# DoorALIM.net
KiCad netlist of a schematic drawn in EAGLE
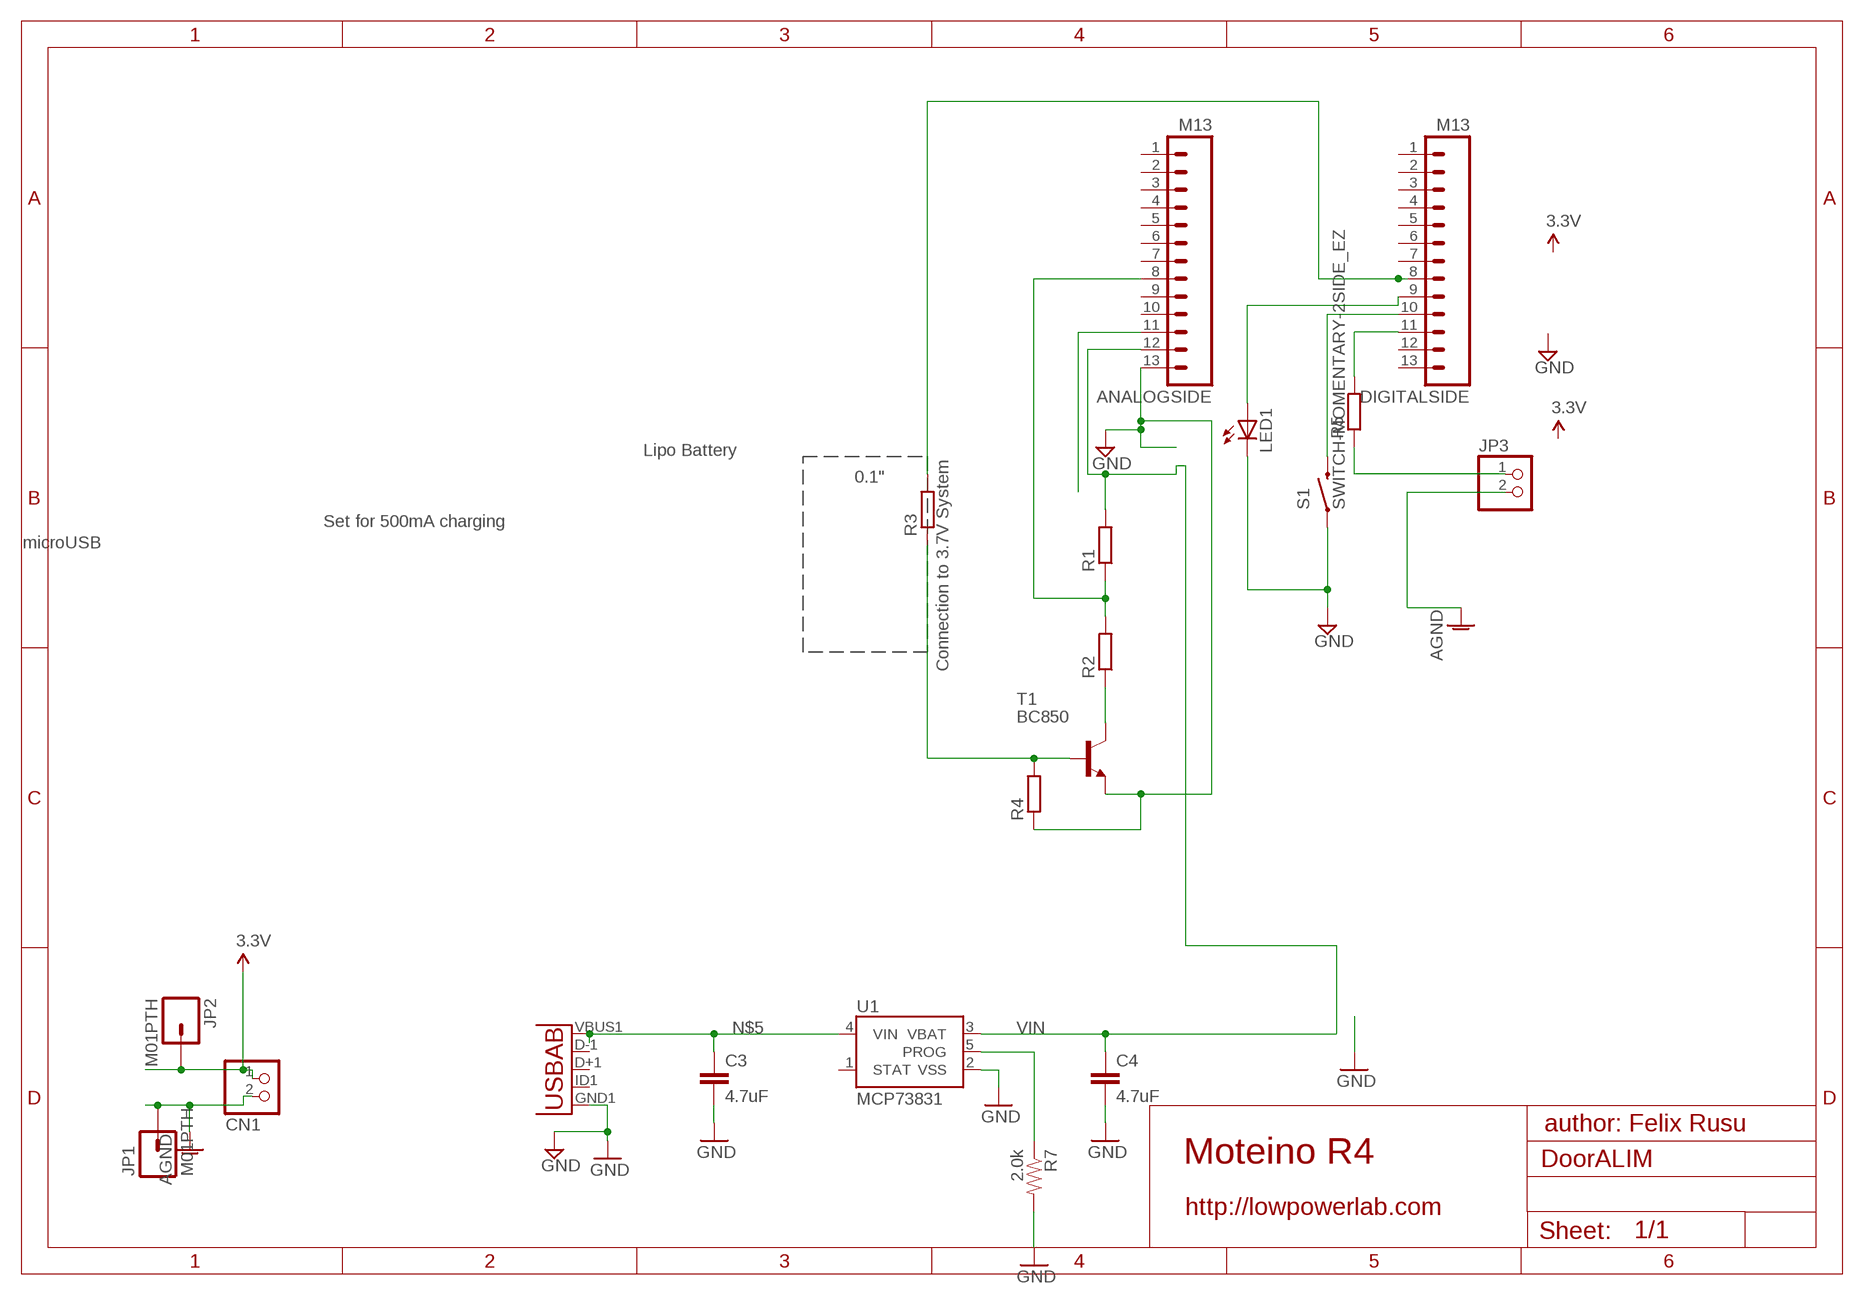
[diagram p0: schematic, sheet 1]

(export (version "E")
  (design (tool "Eeschema 10.0.6"))
  (components
    (comp (ref "ANALOGSIDE")
      (value "M13")
      (footprint "eagle-import:1X13")
      (libsource (lib "eagle-import") (part "M13"))
    )
    (comp (ref "C3")
      (value "4.7uF")
      (footprint "eagle-import:0603-CAP")
      (libsource (lib "eagle-import") (part "4.7UF-6.3V-10%(0603)0603"))
    )
    (comp (ref "C4")
      (value "4.7uF")
      (footprint "eagle-import:0603-CAP")
      (libsource (lib "eagle-import") (part "4.7UF-6.3V-10%(0603)0603"))
    )
    (comp (ref "CN1")
      (value "JST_2PIN-SMT")
      (footprint "eagle-import:JST-PH-2-SMT")
      (libsource (lib "eagle-import") (part "JST_2PIN-SMT"))
    )
    (comp (ref "DIGITALSIDE")
      (value "M13")
      (footprint "eagle-import:1X13")
      (libsource (lib "eagle-import") (part "M13"))
    )
    (comp (ref "JP1")
      (value "M01PTH")
      (footprint "eagle-import:1X01")
      (libsource (lib "eagle-import") (part "M01PTH"))
    )
    (comp (ref "JP2")
      (value "M01PTH")
      (footprint "eagle-import:1X01")
      (libsource (lib "eagle-import") (part "M01PTH"))
    )
    (comp (ref "JP3")
      (value "PINHD-1X2")
      (footprint "eagle-import:1X02")
      (libsource (lib "eagle-import") (part "PINHD-1X2"))
    )
    (comp (ref "JP9")
      (value "Micro USB")
      (footprint "eagle-import:USB-AB-MICRO-SMD_V03")
      (libsource (lib "eagle-import") (part "USB-ABCONN-11794"))
    )
    (comp (ref "LED1")
      (value "LED3MM")
      (footprint "eagle-import:LED3MM")
      (libsource (lib "eagle-import") (part "LED3MM"))
    )
    (comp (ref "R1")
      (value "R-EU_0204/7")
      (footprint "eagle-import:0204_7")
      (libsource (lib "eagle-import") (part "R-EU_0204/7"))
    )
    (comp (ref "R2")
      (value "R-EU_0204/7")
      (footprint "eagle-import:0204_7")
      (libsource (lib "eagle-import") (part "R-EU_0204/7"))
    )
    (comp (ref "R3")
      (value "R-EU_M1206")
      (footprint "eagle-import:M1206")
      (libsource (lib "eagle-import") (part "R-EU_M1206"))
    )
    (comp (ref "R4")
      (value "R-EU_M1206")
      (footprint "eagle-import:M1206")
      (libsource (lib "eagle-import") (part "R-EU_M1206"))
    )
    (comp (ref "R5")
      (value "R-EU_0204/7")
      (footprint "eagle-import:0204_7")
      (libsource (lib "eagle-import") (part "R-EU_0204/7"))
    )
    (comp (ref "R7")
      (value "2.0k")
      (footprint "eagle-import:0603-RES")
      (libsource (lib "eagle-import") (part "2.0KOHM1/10W5%(0603)"))
    )
    (comp (ref "S1")
      (value "SWITCH-MOMENTARY-2SIDE_EZ")
      (footprint "eagle-import:TACTILE-PTH-SIDEEZ")
      (libsource (lib "eagle-import") (part "SWITCH-MOMENTARY-2SIDE_EZ"))
    )
    (comp (ref "T1")
      (value "BC850")
      (footprint "eagle-import:SOT23")
      (libsource (lib "eagle-import") (part "BC850"))
    )
    (comp (ref "U1")
      (value "MCP73831")
      (footprint "eagle-import:SOT23-5")
      (libsource (lib "eagle-import") (part "MCP73831"))
    )
  )
  (nets
    (net (code "1") (name "/N$5") (class "Default")
      (node (ref "C3") (pin "1") (pinfunction "1_1") (pintype "passive"))
      (node (ref "JP9") (pin "VBUS1") (pinfunction "VBUS_VBUS1") (pintype "bidirectional"))
      (node (ref "U1") (pin "4") (pinfunction "VIN_4") (pintype "power_in"))
    )
    (net (code "2") (name "/VIN") (class "Default")
      (node (ref "ANALOGSIDE") (pin "12") (pinfunction "12_12") (pintype "passive"))
      (node (ref "C4") (pin "1") (pinfunction "1_1") (pintype "passive"))
      (node (ref "R1") (pin "2") (pinfunction "2_2") (pintype "passive"))
      (node (ref "U1") (pin "3") (pinfunction "VBAT_3") (pintype "power_in"))
    )
    (net (code "3") (name "3.3V") (class "Default")
      (node (ref "CN1") (pin "1") (pinfunction "2_1") (pintype "passive"))
      (node (ref "JP2") (pin "1") (pinfunction "1_1") (pintype "passive"))
    )
    (net (code "4") (name "AGND") (class "Default")
      (node (ref "CN1") (pin "2") (pinfunction "1_2") (pintype "passive"))
      (node (ref "JP1") (pin "1") (pinfunction "1_1") (pintype "passive"))
      (node (ref "JP3") (pin "2") (pinfunction "2_2") (pintype "passive"))
    )
    (net (code "5") (name "GND") (class "Default")
      (node (ref "ANALOGSIDE") (pin "13") (pinfunction "13_13") (pintype "passive"))
      (node (ref "C3") (pin "2") (pinfunction "2_2") (pintype "passive"))
      (node (ref "C4") (pin "2") (pinfunction "2_2") (pintype "passive"))
      (node (ref "JP9") (pin "GND1") (pinfunction "GND_GND1") (pintype "bidirectional"))
      (node (ref "LED1") (pin "K") (pinfunction "C_K") (pintype "passive"))
      (node (ref "R4") (pin "1") (pinfunction "1_1") (pintype "passive"))
      (node (ref "R7") (pin "2") (pinfunction "2_2") (pintype "passive"))
      (node (ref "S1") (pin "1") (pinfunction "1_1") (pintype "passive"))
      (node (ref "T1") (pin "2") (pinfunction "E_2") (pintype "passive"))
      (node (ref "U1") (pin "2") (pinfunction "VSS_2") (pintype "power_in"))
    )
    (net (code "6") (name "Net-(ANALOGSIDE-Pad8)") (class "Default")
      (node (ref "ANALOGSIDE") (pin "8") (pinfunction "8_8") (pintype "passive"))
      (node (ref "R1") (pin "1") (pinfunction "1_1") (pintype "passive"))
      (node (ref "R2") (pin "2") (pinfunction "2_2") (pintype "passive"))
    )
    (net (code "7") (name "Net-(DIGITALSIDE-Pad8)") (class "Default")
      (node (ref "DIGITALSIDE") (pin "8") (pinfunction "8_8") (pintype "passive"))
      (node (ref "R3") (pin "2") (pinfunction "2_2") (pintype "passive"))
    )
    (net (code "8") (name "Net-(DIGITALSIDE-Pad9)") (class "Default")
      (node (ref "DIGITALSIDE") (pin "9") (pinfunction "9_9") (pintype "passive"))
      (node (ref "LED1") (pin "A") (pinfunction "A_A") (pintype "passive"))
    )
    (net (code "9") (name "Net-(DIGITALSIDE-Pad10)") (class "Default")
      (node (ref "DIGITALSIDE") (pin "10") (pinfunction "10_10") (pintype "passive"))
      (node (ref "S1") (pin "2") (pinfunction "2_2") (pintype "passive"))
    )
    (net (code "10") (name "Net-(DIGITALSIDE-Pad11)") (class "Default")
      (node (ref "DIGITALSIDE") (pin "11") (pinfunction "11_11") (pintype "passive"))
      (node (ref "R5") (pin "2") (pinfunction "2_2") (pintype "passive"))
    )
    (net (code "11") (name "Net-(JP3-Pad1)") (class "Default")
      (node (ref "JP3") (pin "1") (pinfunction "1_1") (pintype "passive"))
      (node (ref "R5") (pin "1") (pinfunction "1_1") (pintype "passive"))
    )
    (net (code "12") (name "Net-(T1-B)") (class "Default")
      (node (ref "R3") (pin "1") (pinfunction "1_1") (pintype "passive"))
      (node (ref "R4") (pin "2") (pinfunction "2_2") (pintype "passive"))
      (node (ref "T1") (pin "1") (pinfunction "B_1") (pintype "passive"))
    )
    (net (code "13") (name "Net-(T1-C)") (class "Default")
      (node (ref "R2") (pin "1") (pinfunction "1_1") (pintype "passive"))
      (node (ref "T1") (pin "3") (pinfunction "C_3") (pintype "passive"))
    )
    (net (code "14") (name "Net-(U1-PROG)") (class "Default")
      (node (ref "R7") (pin "1") (pinfunction "1_1") (pintype "passive"))
      (node (ref "U1") (pin "5") (pinfunction "PROG_5") (pintype "input"))
    )
    (net (code "15") (name "unconnected-(ANALOGSIDE-Pad1)") (class "Default")
      (node (ref "ANALOGSIDE") (pin "1") (pinfunction "1_1") (pintype "passive"))
    )
    (net (code "16") (name "unconnected-(ANALOGSIDE-Pad2)") (class "Default")
      (node (ref "ANALOGSIDE") (pin "2") (pinfunction "2_2") (pintype "passive"))
    )
    (net (code "17") (name "unconnected-(ANALOGSIDE-Pad3)") (class "Default")
      (node (ref "ANALOGSIDE") (pin "3") (pinfunction "3_3") (pintype "passive"))
    )
    (net (code "18") (name "unconnected-(ANALOGSIDE-Pad4)") (class "Default")
      (node (ref "ANALOGSIDE") (pin "4") (pinfunction "4_4") (pintype "passive"))
    )
    (net (code "19") (name "unconnected-(ANALOGSIDE-Pad5)") (class "Default")
      (node (ref "ANALOGSIDE") (pin "5") (pinfunction "5_5") (pintype "passive"))
    )
    (net (code "20") (name "unconnected-(ANALOGSIDE-Pad6)") (class "Default")
      (node (ref "ANALOGSIDE") (pin "6") (pinfunction "6_6") (pintype "passive"))
    )
    (net (code "21") (name "unconnected-(ANALOGSIDE-Pad7)") (class "Default")
      (node (ref "ANALOGSIDE") (pin "7") (pinfunction "7_7") (pintype "passive"))
    )
    (net (code "22") (name "unconnected-(ANALOGSIDE-Pad9)") (class "Default")
      (node (ref "ANALOGSIDE") (pin "9") (pinfunction "9_9") (pintype "passive"))
    )
    (net (code "23") (name "unconnected-(ANALOGSIDE-Pad10)") (class "Default")
      (node (ref "ANALOGSIDE") (pin "10") (pinfunction "10_10") (pintype "passive"))
    )
    (net (code "24") (name "unconnected-(ANALOGSIDE-Pad11)") (class "Default")
      (node (ref "ANALOGSIDE") (pin "11") (pinfunction "11_11") (pintype "passive"))
    )
    (net (code "25") (name "unconnected-(DIGITALSIDE-Pad1)") (class "Default")
      (node (ref "DIGITALSIDE") (pin "1") (pinfunction "1_1") (pintype "passive"))
    )
    (net (code "26") (name "unconnected-(DIGITALSIDE-Pad2)") (class "Default")
      (node (ref "DIGITALSIDE") (pin "2") (pinfunction "2_2") (pintype "passive"))
    )
    (net (code "27") (name "unconnected-(DIGITALSIDE-Pad3)") (class "Default")
      (node (ref "DIGITALSIDE") (pin "3") (pinfunction "3_3") (pintype "passive"))
    )
    (net (code "28") (name "unconnected-(DIGITALSIDE-Pad4)") (class "Default")
      (node (ref "DIGITALSIDE") (pin "4") (pinfunction "4_4") (pintype "passive"))
    )
    (net (code "29") (name "unconnected-(DIGITALSIDE-Pad5)") (class "Default")
      (node (ref "DIGITALSIDE") (pin "5") (pinfunction "5_5") (pintype "passive"))
    )
    (net (code "30") (name "unconnected-(DIGITALSIDE-Pad6)") (class "Default")
      (node (ref "DIGITALSIDE") (pin "6") (pinfunction "6_6") (pintype "passive"))
    )
    (net (code "31") (name "unconnected-(DIGITALSIDE-Pad7)") (class "Default")
      (node (ref "DIGITALSIDE") (pin "7") (pinfunction "7_7") (pintype "passive"))
    )
    (net (code "32") (name "unconnected-(DIGITALSIDE-Pad12)") (class "Default")
      (node (ref "DIGITALSIDE") (pin "12") (pinfunction "12_12") (pintype "passive"))
    )
    (net (code "33") (name "unconnected-(DIGITALSIDE-Pad13)") (class "Default")
      (node (ref "DIGITALSIDE") (pin "13") (pinfunction "13_13") (pintype "passive"))
    )
    (net (code "34") (name "unconnected-(JP9-D+-PadD+1)") (class "Default")
      (node (ref "JP9") (pin "D+1") (pinfunction "D+_D+1") (pintype "bidirectional"))
    )
    (net (code "35") (name "unconnected-(JP9-D--PadD-1)") (class "Default")
      (node (ref "JP9") (pin "D-1") (pinfunction "D-_D-1") (pintype "bidirectional"))
    )
    (net (code "36") (name "unconnected-(JP9-USBID-PadID1)") (class "Default")
      (node (ref "JP9") (pin "ID1") (pinfunction "USBID_ID1") (pintype "bidirectional"))
    )
    (net (code "37") (name "unconnected-(U1-STAT-Pad1)") (class "Default")
      (node (ref "U1") (pin "1") (pinfunction "STAT_1") (pintype "output"))
    )
  )
)
